# 6coils-1-discrete.net
KiCad netlist of a schematic drawn in EasyEDA
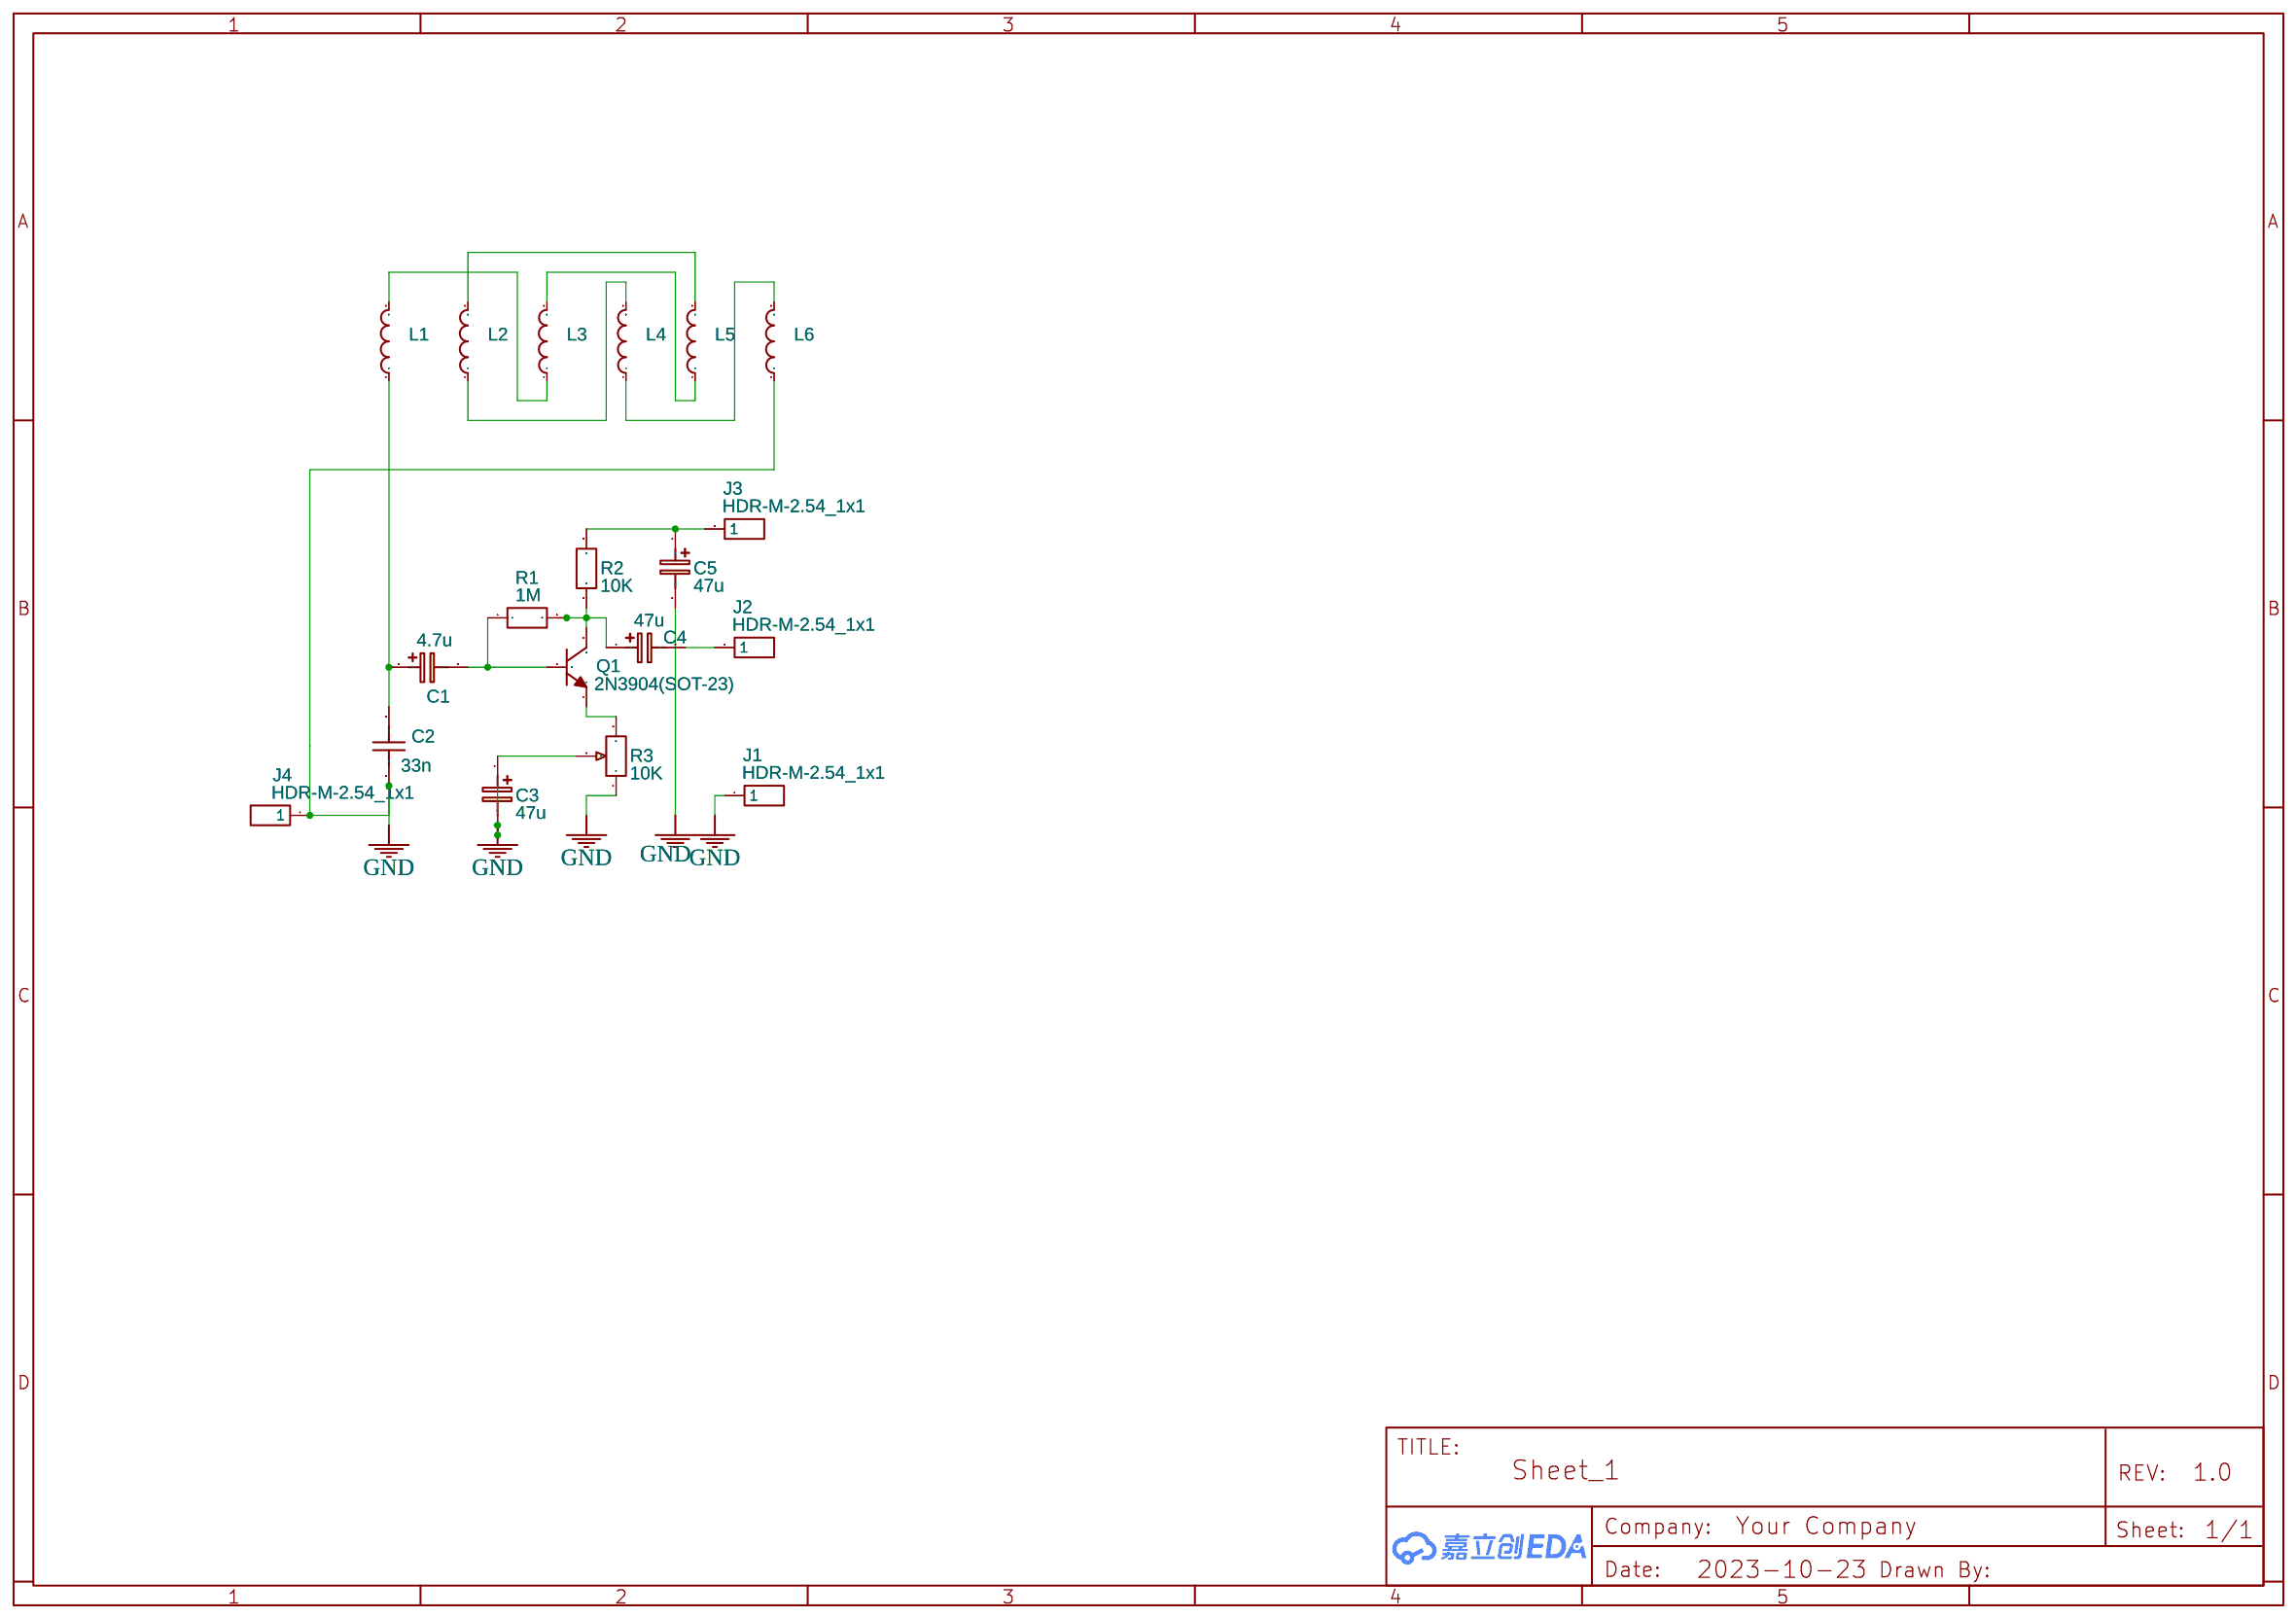
[diagram p0: schematic sheet]

(export (version "E")
  (design (tool "Eeschema 10.0.6"))
  (components
    (comp (ref "C1") (value "4.7u") (libsource (lib "") (part "C_Tan_SMD_A_EU")))
    (comp (ref "C2") (value "33n") (libsource (lib "") (part "C_0603_US")))
    (comp (ref "C3") (value "47u") (libsource (lib "") (part "C_Tan_SMD_A_EU_3")))
    (comp (ref "C4") (value "47u") (libsource (lib "") (part "C_Tan_SMD_A_EU_1")))
    (comp (ref "C5") (value "47u") (libsource (lib "") (part "C_Tan_SMD_A_EU_2")))
    (comp (ref "J1")
      (value "HDR-M-2.54_1x1")
      (fields (field (name "BOM_Supplier Part") "C81276"))
      (libsource (lib "") (part "HDR-M-2.54_1x1_1"))
    )
    (comp (ref "J2")
      (value "HDR-M-2.54_1x1")
      (fields (field (name "BOM_Supplier Part") "C81276"))
      (libsource (lib "") (part "HDR-M-2.54_1x1_1"))
    )
    (comp (ref "J3")
      (value "HDR-M-2.54_1x1")
      (fields (field (name "BOM_Supplier Part") "C81276"))
      (libsource (lib "") (part "HDR-M-2.54_1x1_1"))
    )
    (comp (ref "J4")
      (value "HDR-M-2.54_1x1")
      (fields (field (name "BOM_Supplier Part") "C81276"))
      (libsource (lib "") (part "HDR-M-2.54_1x1"))
    )
    (comp (ref "L1")
      (value "INDUCTOR_SMD:L_COILCRAFT_XXL4040")
      (fields (field (name "Manufacturer Part") "Inductor_SMD:L_Coilcraft_XxL4040"))
      (libsource (lib "") (part "INDUCTOR_SMD{colon}L_COILCRAFT_XXL4040_1"))
    )
    (comp (ref "L2")
      (value "INDUCTOR_SMD:L_COILCRAFT_XXL4040")
      (fields (field (name "Manufacturer Part") "Inductor_SMD:L_Coilcraft_XxL4040"))
      (libsource (lib "") (part "INDUCTOR_SMD{colon}L_COILCRAFT_XXL4040_1"))
    )
    (comp (ref "L3")
      (value "INDUCTOR_SMD:L_COILCRAFT_XXL4040")
      (fields (field (name "Manufacturer Part") "Inductor_SMD:L_Coilcraft_XxL4040"))
      (libsource (lib "") (part "INDUCTOR_SMD{colon}L_COILCRAFT_XXL4040"))
    )
    (comp (ref "L4")
      (value "INDUCTOR_SMD:L_COILCRAFT_XXL4040")
      (fields (field (name "Manufacturer Part") "Inductor_SMD:L_Coilcraft_XxL4040"))
      (libsource (lib "") (part "INDUCTOR_SMD{colon}L_COILCRAFT_XXL4040"))
    )
    (comp (ref "L5")
      (value "INDUCTOR_SMD:L_COILCRAFT_XXL4040")
      (fields (field (name "Manufacturer Part") "Inductor_SMD:L_Coilcraft_XxL4040"))
      (libsource (lib "") (part "INDUCTOR_SMD{colon}L_COILCRAFT_XXL4040"))
    )
    (comp (ref "L6")
      (value "INDUCTOR_SMD:L_COILCRAFT_XXL4040")
      (fields (field (name "Manufacturer Part") "Inductor_SMD:L_Coilcraft_XxL4040"))
      (libsource (lib "") (part "INDUCTOR_SMD{colon}L_COILCRAFT_XXL4040"))
    )
    (comp (ref "Q1")
      (value "2N3904(SOT-23)")
      (fields
        (field (name "BOM_Manufacturer Part") "2n3904S-RTK/PS")
        (field (name "BOM_Supplier Part") "C18536")
      )
      (libsource (lib "") (part "2N3904(SOT-23)"))
    )
    (comp (ref "R1") (value "1M") (libsource (lib "") (part "R_0603_EU")))
    (comp (ref "R2") (value "10K") (libsource (lib "") (part "R_0603_EU_1")))
    (comp (ref "R3")
      (value "10K")
      (fields (field (name "Manufacturer Part") "RM063-103 10K") (field (name "Manufacturer") "JML"))
      (libsource (lib "") (part "RM063-103 10K"))
    )
  )
  (nets
    (net (code "1") (name "GND") (class "Default")
      (node (ref "C2") (pin "1") (pinfunction "1_1") (pintype "unspecified"))
      (node (ref "C3") (pin "2") (pinfunction "2_2") (pintype "unspecified"))
      (node (ref "C5") (pin "2") (pinfunction "2_2") (pintype "unspecified"))
      (node (ref "J1") (pin "1") (pinfunction "1_1") (pintype "input"))
      (node (ref "J4") (pin "1") (pinfunction "1_1") (pintype "input"))
      (node (ref "L6") (pin "1") (pinfunction "1_1") (pintype "unspecified"))
      (node (ref "R3") (pin "1") (pinfunction "1_1") (pintype "input"))
    )
    (net (code "2") (name "Net-(C1-Pad1)") (class "Default")
      (node (ref "C1") (pin "1") (pinfunction "1_1") (pintype "unspecified"))
      (node (ref "C2") (pin "2") (pinfunction "2_2") (pintype "unspecified"))
      (node (ref "L1") (pin "1") (pinfunction "1_1") (pintype "unspecified"))
    )
    (net (code "3") (name "Net-(C3-Pad1)") (class "Default")
      (node (ref "C3") (pin "1") (pinfunction "1_1") (pintype "unspecified"))
      (node (ref "R3") (pin "2") (pinfunction "2_2") (pintype "input"))
    )
    (net (code "4") (name "Net-(C4-Pad2)") (class "Default")
      (node (ref "C4") (pin "2") (pinfunction "2_2") (pintype "unspecified"))
      (node (ref "J2") (pin "1") (pinfunction "1_1") (pintype "input"))
    )
    (net (code "5") (name "Net-(C5-Pad1)") (class "Default")
      (node (ref "C5") (pin "1") (pinfunction "1_1") (pintype "unspecified"))
      (node (ref "J3") (pin "1") (pinfunction "1_1") (pintype "input"))
      (node (ref "R2") (pin "2") (pinfunction "2_2") (pintype "unspecified"))
    )
    (net (code "6") (name "Net-(L1-Pad2)") (class "Default")
      (node (ref "L1") (pin "2") (pinfunction "2_2") (pintype "unspecified"))
      (node (ref "L3") (pin "1") (pinfunction "1_1") (pintype "unspecified"))
    )
    (net (code "7") (name "Net-(L2-Pad1)") (class "Default")
      (node (ref "L2") (pin "1") (pinfunction "1_1") (pintype "unspecified"))
      (node (ref "L4") (pin "2") (pinfunction "2_2") (pintype "unspecified"))
    )
    (net (code "8") (name "Net-(L2-Pad2)") (class "Default")
      (node (ref "L2") (pin "2") (pinfunction "2_2") (pintype "unspecified"))
      (node (ref "L5") (pin "2") (pinfunction "2_2") (pintype "unspecified"))
    )
    (net (code "9") (name "Net-(L3-Pad2)") (class "Default")
      (node (ref "L3") (pin "2") (pinfunction "2_2") (pintype "unspecified"))
      (node (ref "L5") (pin "1") (pinfunction "1_1") (pintype "unspecified"))
    )
    (net (code "10") (name "Net-(L4-Pad1)") (class "Default")
      (node (ref "L4") (pin "1") (pinfunction "1_1") (pintype "unspecified"))
      (node (ref "L6") (pin "2") (pinfunction "2_2") (pintype "unspecified"))
    )
    (net (code "11") (name "Net-(Q1-B)") (class "Default")
      (node (ref "C1") (pin "2") (pinfunction "2_2") (pintype "unspecified"))
      (node (ref "Q1") (pin "2") (pinfunction "B_2") (pintype "input"))
      (node (ref "R1") (pin "1") (pinfunction "1_1") (pintype "unspecified"))
    )
    (net (code "12") (name "Net-(Q1-C)") (class "Default")
      (node (ref "C4") (pin "1") (pinfunction "1_1") (pintype "unspecified"))
      (node (ref "Q1") (pin "3") (pinfunction "C_3") (pintype "input"))
      (node (ref "R1") (pin "2") (pinfunction "2_2") (pintype "unspecified"))
      (node (ref "R2") (pin "1") (pinfunction "1_1") (pintype "unspecified"))
    )
    (net (code "13") (name "Net-(Q1-E)") (class "Default")
      (node (ref "Q1") (pin "1") (pinfunction "E_1") (pintype "input"))
      (node (ref "R3") (pin "3") (pinfunction "3_3") (pintype "input"))
    )
  )
)
